# GSMGPSMC60.net
KiCad netlist of a schematic drawn in Altium Designer
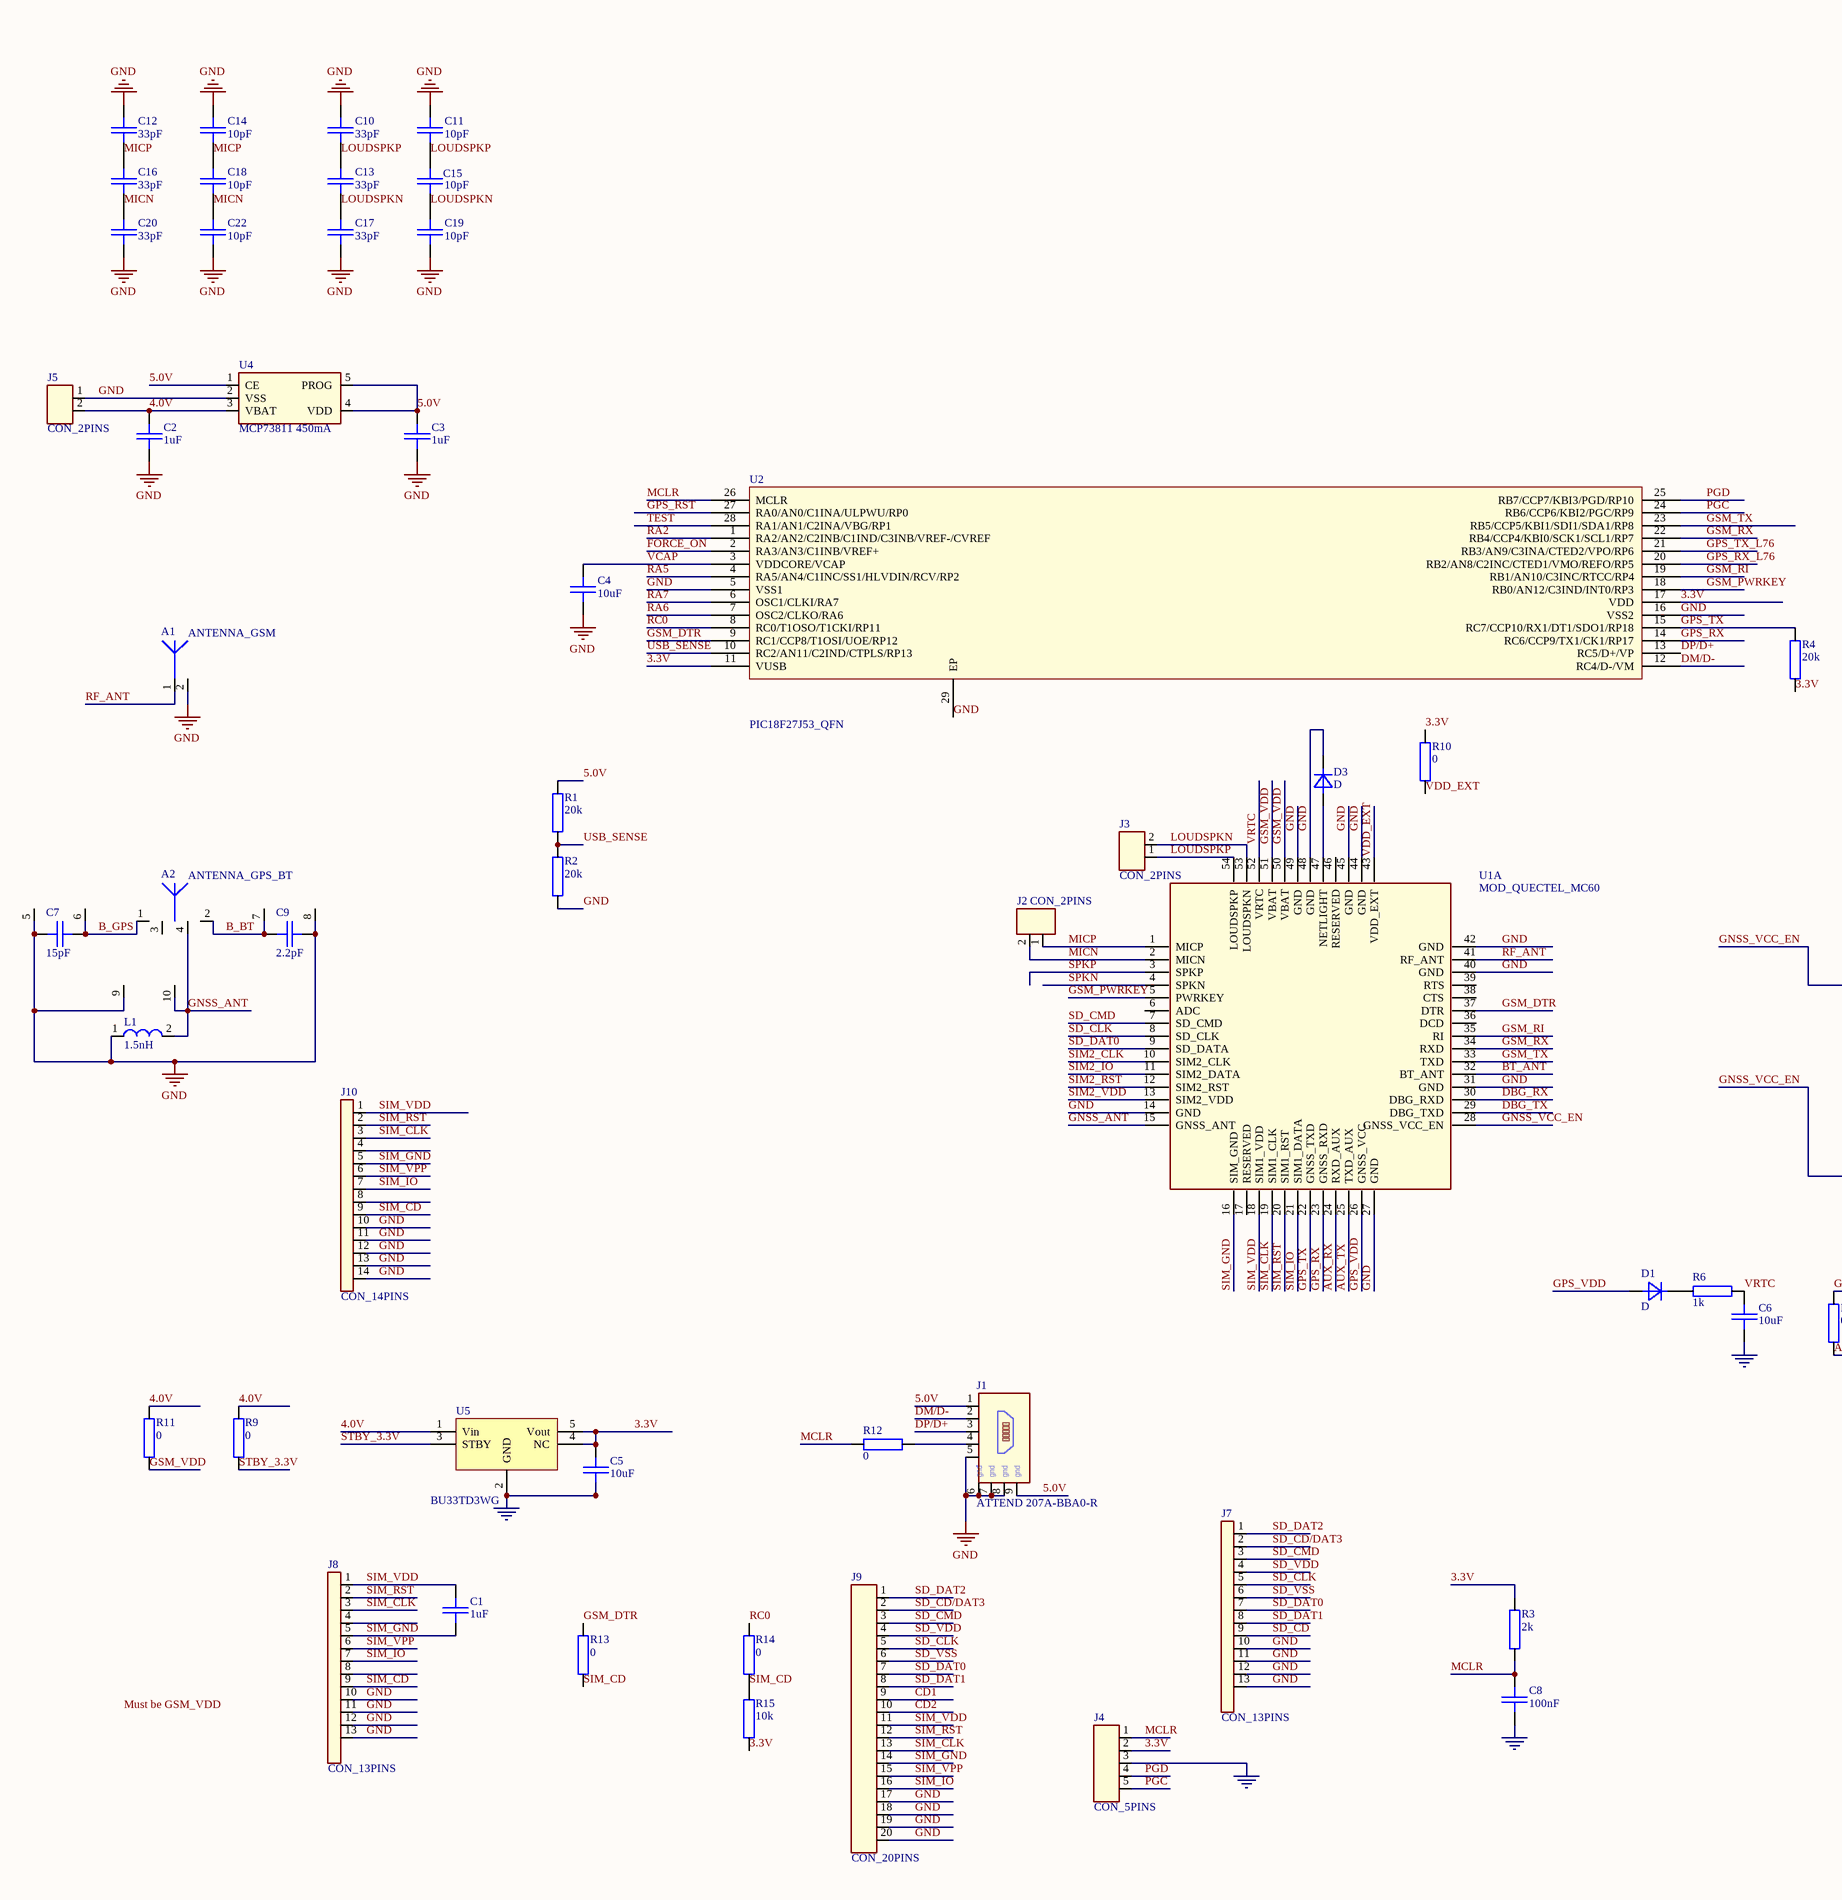
[diagram p0: GSMGPSMC60.SchDoc, left]
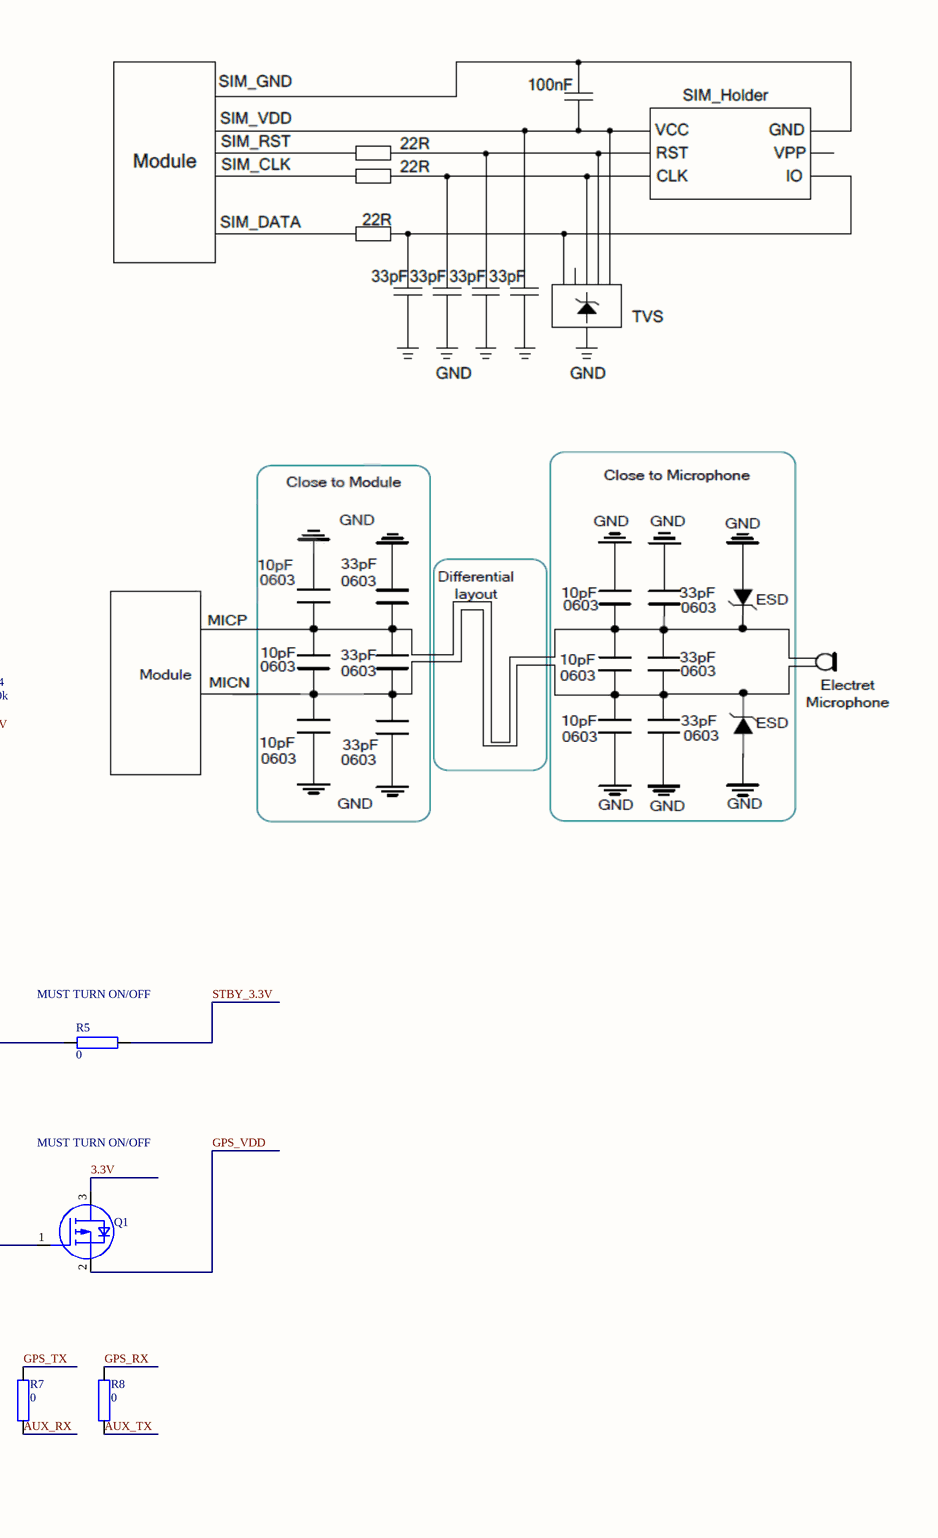
[diagram p1: GSMGPSMC60.SchDoc, right]

(export (version "E")
  (design (tool "Eeschema 10.0.6"))
  (components
    (comp (ref "A1")
      (value "ANTENNA_GSM")
      (footprint "SMD_CON_ANTENNA_GSM")
      (libsource (lib "DLV") (part "ANTENNA_2"))
    )
    (comp (ref "A2")
      (value "ANTENNA_GPS_BT")
      (footprint "SMD_CHIP_ANTENNA_GPS_BT - FLIP")
      (libsource (lib "DLV") (part "ANTENNA_GPS_BT"))
    )
    (comp (ref "C1") (value "1uF") (footprint "SMD_0603_CAPC1608X95N") (libsource (lib "DLV") (part "C")))
    (comp (ref "C2") (value "1uF") (footprint "SMD_0603_CAPC1608X95N") (libsource (lib "DLV") (part "C")))
    (comp (ref "C3") (value "1uF") (footprint "SMD_0603_CAPC1608X95N") (libsource (lib "DLV") (part "C")))
    (comp (ref "C4") (value "10uF") (footprint "SMD_0603_CAPC1608X95N") (libsource (lib "DLV") (part "C")))
    (comp (ref "C5") (value "10uF") (footprint "SMD_0603_CAPC1608X95N") (libsource (lib "DLV") (part "C")))
    (comp (ref "C6") (value "10uF") (footprint "SMD_0603_CAPC1608X95N") (libsource (lib "DLV") (part "C")))
    (comp (ref "C7")
      (value "15pF")
      (footprint "SMD_0402_CAPC1005X90N - ANTENNA")
      (libsource (lib "DLV") (part "C"))
    )
    (comp (ref "C8") (value "100nF") (footprint "SMD_0402_CAPC1005X90N") (libsource (lib "DLV") (part "C")))
    (comp (ref "C9")
      (value "2.2pF")
      (footprint "SMD_0201_CAPC0603X33N - ANTENNA")
      (libsource (lib "DLV") (part "C"))
    )
    (comp (ref "C10") (value "33pF") (footprint "SMD_0402_CAPC1005X90N") (libsource (lib "DLV") (part "C")))
    (comp (ref "C11") (value "10pF") (footprint "SMD_0402_CAPC1005X90N") (libsource (lib "DLV") (part "C")))
    (comp (ref "C12") (value "33pF") (footprint "SMD_0402_CAPC1005X90N") (libsource (lib "DLV") (part "C")))
    (comp (ref "C13") (value "33pF") (footprint "SMD_0402_CAPC1005X90N") (libsource (lib "DLV") (part "C")))
    (comp (ref "C14") (value "10pF") (footprint "SMD_0402_CAPC1005X90N") (libsource (lib "DLV") (part "C")))
    (comp (ref "C15") (value "10pF") (footprint "SMD_0402_CAPC1005X90N") (libsource (lib "DLV") (part "C")))
    (comp (ref "C16") (value "33pF") (footprint "SMD_0402_CAPC1005X90N") (libsource (lib "DLV") (part "C")))
    (comp (ref "C17") (value "33pF") (footprint "SMD_0402_CAPC1005X90N") (libsource (lib "DLV") (part "C")))
    (comp (ref "C18") (value "10pF") (footprint "SMD_0402_CAPC1005X90N") (libsource (lib "DLV") (part "C")))
    (comp (ref "C19") (value "10pF") (footprint "SMD_0402_CAPC1005X90N") (libsource (lib "DLV") (part "C")))
    (comp (ref "C20") (value "33pF") (footprint "SMD_0402_CAPC1005X90N") (libsource (lib "DLV") (part "C")))
    (comp (ref "C22") (value "10pF") (footprint "SMD_0402_CAPC1005X90N") (libsource (lib "DLV") (part "C")))
    (comp (ref "D1") (value "D") (footprint "SMD_SOD523_SOD1608X65N") (libsource (lib "DLV") (part "D")))
    (comp (ref "D3") (value "D") (footprint "SMD_LED_LAA67F") (libsource (lib "DLV") (part "D")))
    (comp (ref "J1")
      (value "ATTEND 207A-BBA0-R")
      (footprint "SMD_CON_MICRO_USB")
      (libsource (lib "DLV") (part "CON_USB_MINI"))
    )
    (comp (ref "J2")
      (value "CON_2PINS")
      (footprint "PTH_MIC_6MM_2.7MM_PITCH1.9")
      (libsource (lib "") (part "CON_2PINS_1"))
    )
    (comp (ref "J3")
      (value "CON_2PINS")
      (footprint "PTH_MIC_6MM_2.7MM_PITCH1.9")
      (libsource (lib "") (part "CON_2PINS_2"))
    )
    (comp (ref "J4") (value "CON_5PINS") (footprint "SIP5 - PGM") (libsource (lib "DLV") (part "CON_5PINS")))
    (comp (ref "J5")
      (value "CON_2PINS")
      (footprint "PTH_HDRV02W64P254_1X02")
      (libsource (lib "DLV") (part "CON_2PINS"))
    )
    (comp (ref "J7") (value "CON_13PINS") (footprint "NONE") (libsource (lib "DLV") (part "CON_13PINS")))
    (comp (ref "J8")
      (value "CON_13PINS")
      (footprint "SMD_CON-ATTEND_MICRO_SIM_115Q-BCA0")
      (libsource (lib "DLV") (part "CON_13PINS"))
    )
    (comp (ref "J9") (value "CON_20PINS") (footprint "NONE") (libsource (lib "DLV") (part "CON_20PINS")))
    (comp (ref "J10") (value "CON_14PINS") (footprint "NONE") (libsource (lib "DLV") (part "CON_14PINS")))
    (comp (ref "L1")
      (value "1.5nH")
      (footprint "SMD_0402_INDC1005X55N - ANTENNA")
      (libsource (lib "DLV") (part "L"))
    )
    (comp (ref "Q1")
      (value "BSH202")
      (footprint "SMD_SOT23_SOT95P240X120-3N")
      (fields
        (field (name "DB_PART_NUMBER") "TRA000000687")
        (field (name "DB_MANUFACTURER_PART") "NXP        BSH202")
      )
      (libsource (lib "EPIQ_DND_CIS") (part "MOS_P_D1_G1S2D3"))
    )
    (comp (ref "R1") (value "20k") (footprint "SMD_0402_RESC1005X37N") (libsource (lib "DLV") (part "R")))
    (comp (ref "R2") (value "20k") (footprint "SMD_0402_RESC1005X37N") (libsource (lib "DLV") (part "R")))
    (comp (ref "R3") (value "2k") (footprint "SMD_0402_RESC1005X37N") (libsource (lib "DLV") (part "R")))
    (comp (ref "R4") (value "20k") (footprint "SMD_0402_RESC1005X37N") (libsource (lib "DLV") (part "R")))
    (comp (ref "R5") (value "0") (footprint "SMD_0402_RESC1005X37N") (libsource (lib "DLV") (part "R")))
    (comp (ref "R6") (value "1k") (footprint "SMD_0603_RESC1608X55N") (libsource (lib "DLV") (part "R")))
    (comp (ref "R7") (value "0") (footprint "SMD_0603_RESC1608X55N") (libsource (lib "DLV") (part "R")))
    (comp (ref "R8") (value "0") (footprint "SMD_0603_RESC1608X55N") (libsource (lib "DLV") (part "R")))
    (comp (ref "R9") (value "0") (footprint "SMD_0402_RESC1005X37N") (libsource (lib "DLV") (part "R")))
    (comp (ref "R10") (value "0") (footprint "SMD_0402_RESC1005X37N") (libsource (lib "DLV") (part "R")))
    (comp (ref "R11") (value "0") (footprint "SMD_0402_RESC1005X37N") (libsource (lib "DLV") (part "R")))
    (comp (ref "R12") (value "0") (footprint "SMD_0402_RESC1005X37N") (libsource (lib "DLV") (part "R")))
    (comp (ref "R13") (value "0") (footprint "SMD_0402_RESC1005X37N") (libsource (lib "DLV") (part "R")))
    (comp (ref "R14") (value "0") (footprint "SMD_0402_RESC1005X37N") (libsource (lib "DLV") (part "R")))
    (comp (ref "R15") (value "10k") (footprint "SMD_0402_RESC1005X37N") (libsource (lib "DLV") (part "R")))
    (comp (ref "U1")
      (value "MOD_QUECTEL_MC60")
      (footprint "SMD_MOD_MC60")
      (libsource (lib "DLV") (part "MOD_QUECTEL_MC60"))
    )
    (comp (ref "U2")
      (value "PIC18F27J53_QFN")
      (footprint "SMD_QFN65P600X600X100-29AN")
      (libsource (lib "DLV") (part "IC_PIC18F27J53_QFN"))
    )
    (comp (ref "U4")
      (value "MCP73811 450mA")
      (footprint "SMD_SOT26_SOT95P285X140-5N - DLV")
      (description "MCP73812")
      (fields
        (field (name "DB_PART_NUMBER") "PSU000000127")
        (field (name "DB_MANUFACTURER_PART") "ROHM        BD33KA5WF-E2")
        (field (name "DB_APPROVED_BY") "VSN")
      )
      (libsource (lib "DLV") (part "IC_MCP73812"))
    )
    (comp (ref "U5")
      (value "BU33TD3WG")
      (footprint "SMD_SOT26_SOT95P285X140-5N - DLV")
      (libsource (lib "DLV") (part "IC_BU33TD3WG"))
    )
  )
  (nets
    (net (code "1") (name "/3.3V") (class "Default")
      (node (ref "C5") (pin "1") (pinfunction "1_1") (pintype "passive"))
      (node (ref "J4") (pin "2") (pinfunction "2_2") (pintype "passive"))
      (node (ref "Q1") (pin "3") (pinfunction "D_3") (pintype "passive"))
      (node (ref "R10") (pin "2") (pinfunction "2_2") (pintype "passive"))
      (node (ref "R15") (pin "2") (pinfunction "2_2") (pintype "passive"))
      (node (ref "R3") (pin "1") (pinfunction "1_1") (pintype "passive"))
      (node (ref "R4") (pin "1") (pinfunction "1_1") (pintype "passive"))
      (node (ref "U2") (pin "11") (pinfunction "VUSB_11") (pintype "passive"))
      (node (ref "U2") (pin "17") (pinfunction "VDD_17") (pintype "passive"))
      (node (ref "U5") (pin "4") (pinfunction "NC_4") (pintype "passive"))
      (node (ref "U5") (pin "5") (pinfunction "Vout_5") (pintype "passive"))
    )
    (net (code "2") (name "/4.0V") (class "Default")
      (node (ref "C2") (pin "1") (pinfunction "1_1") (pintype "passive"))
      (node (ref "J5") (pin "2") (pinfunction "2_2") (pintype "passive"))
      (node (ref "R11") (pin "1") (pinfunction "1_1") (pintype "passive"))
      (node (ref "R9") (pin "1") (pinfunction "1_1") (pintype "passive"))
      (node (ref "U4") (pin "3") (pinfunction "VBAT_3") (pintype "passive"))
      (node (ref "U5") (pin "1") (pinfunction "Vin_1") (pintype "passive"))
    )
    (net (code "3") (name "/5.0V") (class "Default")
      (node (ref "C3") (pin "1") (pinfunction "1_1") (pintype "passive"))
      (node (ref "J1") (pin "1") (pinfunction "1_1") (pintype "passive"))
      (node (ref "J1") (pin "9") (pinfunction "9_9") (pintype "passive"))
      (node (ref "R1") (pin "2") (pinfunction "2_2") (pintype "passive"))
      (node (ref "U4") (pin "1") (pinfunction "CE_1") (pintype "passive"))
      (node (ref "U4") (pin "4") (pinfunction "VDD_4") (pintype "passive"))
      (node (ref "U4") (pin "5") (pinfunction "PROG_5") (pintype "passive"))
    )
    (net (code "4") (name "/AUX_RX") (class "Default")
      (node (ref "R7") (pin "2") (pinfunction "2_2") (pintype "passive"))
      (node (ref "U1") (pin "24") (pinfunction "RXD_AUX_24") (pintype "passive"))
    )
    (net (code "5") (name "/AUX_TX") (class "Default")
      (node (ref "R8") (pin "1") (pinfunction "1_1") (pintype "passive"))
      (node (ref "U1") (pin "25") (pinfunction "TXD_AUX_25") (pintype "passive"))
    )
    (net (code "6") (name "/BT_ANT") (class "Default")
      (node (ref "U1") (pin "32") (pinfunction "BT_ANT_32") (pintype "passive"))
    )
    (net (code "7") (name "/B_BT") (class "Default")
      (node (ref "A2") (pin "2") (pinfunction "2_2") (pintype "passive"))
      (node (ref "A2") (pin "7") (pinfunction "7_7") (pintype "passive"))
      (node (ref "C9") (pin "1") (pinfunction "1_1") (pintype "passive"))
    )
    (net (code "8") (name "/B_GPS") (class "Default")
      (node (ref "A2") (pin "1") (pinfunction "1_1") (pintype "passive"))
      (node (ref "A2") (pin "6") (pinfunction "6_6") (pintype "passive"))
      (node (ref "C7") (pin "2") (pinfunction "2_2") (pintype "passive"))
    )
    (net (code "9") (name "/CD1") (class "Default")
      (node (ref "J9") (pin "9") (pinfunction "9_9") (pintype "passive"))
    )
    (net (code "10") (name "/CD2") (class "Default")
      (node (ref "J9") (pin "10") (pinfunction "10_10") (pintype "passive"))
    )
    (net (code "11") (name "/DBG_RX") (class "Default")
      (node (ref "U1") (pin "30") (pinfunction "DBG_RXD_30") (pintype "passive"))
    )
    (net (code "12") (name "/DBG_TX") (class "Default")
      (node (ref "U1") (pin "29") (pinfunction "DBG_TXD_29") (pintype "passive"))
    )
    (net (code "13") (name "/DM{slash}D-") (class "Default")
      (node (ref "J1") (pin "2") (pinfunction "2_2") (pintype "passive"))
      (node (ref "U2") (pin "12") (pinfunction "RC4/D-/VM_12") (pintype "passive"))
    )
    (net (code "14") (name "/DP{slash}D+") (class "Default")
      (node (ref "J1") (pin "3") (pinfunction "3_3") (pintype "passive"))
      (node (ref "U2") (pin "13") (pinfunction "RC5/D+/VP_13") (pintype "passive"))
    )
    (net (code "15") (name "/FORCE_ON") (class "Default")
      (node (ref "U2") (pin "2") (pinfunction "RA3/AN3/C1INB/VREF+_2") (pintype "passive"))
    )
    (net (code "16") (name "/GNSS_ANT") (class "Default")
      (node (ref "A2") (pin "10") (pinfunction "10_10") (pintype "passive"))
      (node (ref "A2") (pin "4") (pinfunction "4_4") (pintype "passive"))
      (node (ref "L1") (pin "2") (pinfunction "2_2") (pintype "passive"))
      (node (ref "U1") (pin "15") (pinfunction "GNSS_ANT_15") (pintype "passive"))
    )
    (net (code "17") (name "/GNSS_VCC_EN") (class "Default")
      (node (ref "Q1") (pin "1") (pinfunction "G_1") (pintype "passive"))
      (node (ref "R5") (pin "1") (pinfunction "1_1") (pintype "passive"))
      (node (ref "U1") (pin "28") (pinfunction "GNSS_VCC_EN_28") (pintype "passive"))
    )
    (net (code "18") (name "/GPS_RST") (class "Default")
      (node (ref "U2") (pin "27") (pinfunction "RA0/AN0/C1INA/ULPWU/RP0_27") (pintype "passive"))
    )
    (net (code "19") (name "/GPS_RX") (class "Default")
      (node (ref "R8") (pin "2") (pinfunction "2_2") (pintype "passive"))
      (node (ref "U1") (pin "23") (pinfunction "GNSS_RXD_23") (pintype "passive"))
      (node (ref "U2") (pin "14") (pinfunction "RC6/CCP9/TX1/CK1/RP17_14") (pintype "passive"))
    )
    (net (code "20") (name "/GPS_RX_L76") (class "Default")
      (node (ref "U2") (pin "20") (pinfunction "RB2/AN8/C2INC/CTED1/VMO/REFO/RP5_20") (pintype "passive"))
    )
    (net (code "21") (name "/GPS_TX") (class "Default")
      (node (ref "R4") (pin "2") (pinfunction "2_2") (pintype "passive"))
      (node (ref "R7") (pin "1") (pinfunction "1_1") (pintype "passive"))
      (node (ref "U1") (pin "22") (pinfunction "GNSS_TXD_22") (pintype "passive"))
      (node (ref "U2") (pin "15") (pinfunction "RC7/CCP10/RX1/DT1/SDO1/RP18_15") (pintype "passive"))
    )
    (net (code "22") (name "/GPS_TX_L76") (class "Default")
      (node (ref "U2") (pin "21") (pinfunction "RB3/AN9/C3INA/CTED2/VPO/RP6_21") (pintype "passive"))
    )
    (net (code "23") (name "/GPS_VDD") (class "Default")
      (node (ref "D1") (pin "2") (pinfunction "A_2") (pintype "passive"))
      (node (ref "Q1") (pin "2") (pinfunction "S_2") (pintype "passive"))
      (node (ref "U1") (pin "26") (pinfunction "GNSS_VCC_26") (pintype "passive"))
    )
    (net (code "24") (name "/GSM_DTR") (class "Default")
      (node (ref "R13") (pin "1") (pinfunction "1_1") (pintype "passive"))
      (node (ref "U1") (pin "37") (pinfunction "DTR_37") (pintype "passive"))
      (node (ref "U2") (pin "9") (pinfunction "RC1/CCP8/T1OSI/UOE/RP12_9") (pintype "passive"))
    )
    (net (code "25") (name "/GSM_PWRKEY") (class "Default")
      (node (ref "U1") (pin "5") (pinfunction "PWRKEY_5") (pintype "passive"))
      (node (ref "U2") (pin "18") (pinfunction "RB0/AN12/C3IND/INT0/RP3_18") (pintype "passive"))
    )
    (net (code "26") (name "/GSM_RI") (class "Default")
      (node (ref "U1") (pin "35") (pinfunction "RI_35") (pintype "passive"))
      (node (ref "U2") (pin "19") (pinfunction "RB1/AN10/C3INC/RTCC/RP4_19") (pintype "passive"))
    )
    (net (code "27") (name "/GSM_RX") (class "Default")
      (node (ref "U1") (pin "34") (pinfunction "RXD_34") (pintype "passive"))
      (node (ref "U2") (pin "22") (pinfunction "RB4/CCP4/KBI0/SCK1/SCL1/RP7_22") (pintype "passive"))
    )
    (net (code "28") (name "/GSM_TX") (class "Default")
      (node (ref "U1") (pin "33") (pinfunction "TXD_33") (pintype "passive"))
      (node (ref "U2") (pin "23") (pinfunction "RB5/CCP5/KBI1/SDI1/SDA1/RP8_23") (pintype "passive"))
    )
    (net (code "29") (name "/GSM_VDD") (class "Default")
      (node (ref "R11") (pin "2") (pinfunction "2_2") (pintype "passive"))
      (node (ref "U1") (pin "50") (pinfunction "VBAT_50") (pintype "passive"))
      (node (ref "U1") (pin "51") (pinfunction "VBAT_51") (pintype "passive"))
    )
    (net (code "30") (name "/LOUDSPKN") (class "Default")
      (node (ref "C13") (pin "2") (pinfunction "2_2") (pintype "passive"))
      (node (ref "C15") (pin "2") (pinfunction "2_2") (pintype "passive"))
      (node (ref "C17") (pin "1") (pinfunction "1_1") (pintype "passive"))
      (node (ref "C19") (pin "1") (pinfunction "1_1") (pintype "passive"))
      (node (ref "J3") (pin "2") (pinfunction "2_2") (pintype "passive"))
      (node (ref "U1") (pin "53") (pinfunction "LOUDSPKN_53") (pintype "passive"))
    )
    (net (code "31") (name "/LOUDSPKP") (class "Default")
      (node (ref "C10") (pin "2") (pinfunction "2_2") (pintype "passive"))
      (node (ref "C11") (pin "2") (pinfunction "2_2") (pintype "passive"))
      (node (ref "C13") (pin "1") (pinfunction "1_1") (pintype "passive"))
      (node (ref "C15") (pin "1") (pinfunction "1_1") (pintype "passive"))
      (node (ref "J3") (pin "1") (pinfunction "1_1") (pintype "passive"))
      (node (ref "U1") (pin "54") (pinfunction "LOUDSPKP_54") (pintype "passive"))
    )
    (net (code "32") (name "/MCLR") (class "Default")
      (node (ref "C8") (pin "1") (pinfunction "1_1") (pintype "passive"))
      (node (ref "J4") (pin "1") (pinfunction "1_1") (pintype "passive"))
      (node (ref "R12") (pin "2") (pinfunction "2_2") (pintype "passive"))
      (node (ref "R3") (pin "2") (pinfunction "2_2") (pintype "passive"))
      (node (ref "U2") (pin "26") (pinfunction "MCLR_26") (pintype "passive"))
    )
    (net (code "33") (name "/MICN") (class "Default")
      (node (ref "C16") (pin "2") (pinfunction "2_2") (pintype "passive"))
      (node (ref "C18") (pin "2") (pinfunction "2_2") (pintype "passive"))
      (node (ref "C20") (pin "1") (pinfunction "1_1") (pintype "passive"))
      (node (ref "C22") (pin "1") (pinfunction "1_1") (pintype "passive"))
      (node (ref "J2") (pin "2") (pinfunction "2_2") (pintype "passive"))
      (node (ref "U1") (pin "2") (pinfunction "MICN_2") (pintype "passive"))
    )
    (net (code "34") (name "/MICP") (class "Default")
      (node (ref "C12") (pin "2") (pinfunction "2_2") (pintype "passive"))
      (node (ref "C14") (pin "2") (pinfunction "2_2") (pintype "passive"))
      (node (ref "C16") (pin "1") (pinfunction "1_1") (pintype "passive"))
      (node (ref "C18") (pin "1") (pinfunction "1_1") (pintype "passive"))
      (node (ref "J2") (pin "1") (pinfunction "1_1") (pintype "passive"))
      (node (ref "U1") (pin "1") (pinfunction "MICP_1") (pintype "passive"))
    )
    (net (code "36") (name "/PGC") (class "Default")
      (node (ref "J4") (pin "5") (pinfunction "5_5") (pintype "passive"))
      (node (ref "U2") (pin "24") (pinfunction "RB6/CCP6/KBI2/PGC/RP9_24") (pintype "passive"))
    )
    (net (code "37") (name "/PGD") (class "Default")
      (node (ref "J4") (pin "4") (pinfunction "4_4") (pintype "passive"))
      (node (ref "U2") (pin "25") (pinfunction "RB7/CCP7/KBI3/PGD/RP10_25") (pintype "passive"))
    )
    (net (code "38") (name "/RA2") (class "Default")
      (node (ref "U2") (pin "1") (pinfunction "RA2/AN2/C2INB/C1IND/C3INB/VREF-/CVREF_1") (pintype "passive"))
    )
    (net (code "39") (name "/RA5") (class "Default")
      (node (ref "U2") (pin "4") (pinfunction "RA5/AN4/C1INC/SS1/HLVDIN/RCV/RP2_4") (pintype "passive"))
    )
    (net (code "40") (name "/RA6") (class "Default")
      (node (ref "U2") (pin "7") (pinfunction "OSC2/CLKO/RA6_7") (pintype "passive"))
    )
    (net (code "41") (name "/RA7") (class "Default")
      (node (ref "U2") (pin "6") (pinfunction "OSC1/CLKI/RA7_6") (pintype "passive"))
    )
    (net (code "42") (name "/RC0") (class "Default")
      (node (ref "R14") (pin "1") (pinfunction "1_1") (pintype "passive"))
      (node (ref "U2") (pin "8") (pinfunction "RC0/T1OSO/T1CKI/RP11_8") (pintype "passive"))
    )
    (net (code "43") (name "/RF_ANT") (class "Default")
      (node (ref "A1") (pin "1") (pinfunction "1_1") (pintype "passive"))
      (node (ref "U1") (pin "41") (pinfunction "RF_ANT_41") (pintype "passive"))
    )
    (net (code "44") (name "/SD_CD") (class "Default")
      (node (ref "J7") (pin "9") (pinfunction "9_9") (pintype "passive"))
    )
    (net (code "45") (name "/SD_CD{slash}DAT3") (class "Default")
      (node (ref "J7") (pin "2") (pinfunction "2_2") (pintype "passive"))
      (node (ref "J9") (pin "2") (pinfunction "2_2") (pintype "passive"))
    )
    (net (code "46") (name "/SD_CLK") (class "Default")
      (node (ref "J7") (pin "5") (pinfunction "5_5") (pintype "passive"))
      (node (ref "J9") (pin "5") (pinfunction "5_5") (pintype "passive"))
      (node (ref "U1") (pin "8") (pinfunction "SD_CLK_8") (pintype "passive"))
    )
    (net (code "47") (name "/SD_CMD") (class "Default")
      (node (ref "J7") (pin "3") (pinfunction "3_3") (pintype "passive"))
      (node (ref "J9") (pin "3") (pinfunction "3_3") (pintype "passive"))
      (node (ref "U1") (pin "7") (pinfunction "SD_CMD_7") (pintype "passive"))
    )
    (net (code "48") (name "/SD_DAT0") (class "Default")
      (node (ref "J7") (pin "7") (pinfunction "7_7") (pintype "passive"))
      (node (ref "J9") (pin "7") (pinfunction "7_7") (pintype "passive"))
      (node (ref "U1") (pin "9") (pinfunction "SD_DATA_9") (pintype "passive"))
    )
    (net (code "49") (name "/SD_DAT1") (class "Default")
      (node (ref "J7") (pin "8") (pinfunction "8_8") (pintype "passive"))
      (node (ref "J9") (pin "8") (pinfunction "8_8") (pintype "passive"))
    )
    (net (code "50") (name "/SD_DAT2") (class "Default")
      (node (ref "J7") (pin "1") (pinfunction "1_1") (pintype "passive"))
      (node (ref "J9") (pin "1") (pinfunction "1_1") (pintype "passive"))
    )
    (net (code "51") (name "/SD_VDD") (class "Default")
      (node (ref "J7") (pin "4") (pinfunction "4_4") (pintype "passive"))
      (node (ref "J9") (pin "4") (pinfunction "4_4") (pintype "passive"))
    )
    (net (code "52") (name "/SD_VSS") (class "Default")
      (node (ref "J7") (pin "6") (pinfunction "6_6") (pintype "passive"))
      (node (ref "J9") (pin "6") (pinfunction "6_6") (pintype "passive"))
    )
    (net (code "53") (name "/SIM2_CLK") (class "Default")
      (node (ref "U1") (pin "10") (pinfunction "SIM2_CLK_10") (pintype "passive"))
    )
    (net (code "54") (name "/SIM2_IO") (class "Default")
      (node (ref "U1") (pin "11") (pinfunction "SIM2_DATA_11") (pintype "passive"))
    )
    (net (code "55") (name "/SIM2_RST") (class "Default")
      (node (ref "U1") (pin "12") (pinfunction "SIM2_RST_12") (pintype "passive"))
    )
    (net (code "56") (name "/SIM2_VDD") (class "Default")
      (node (ref "U1") (pin "13") (pinfunction "SIM2_VDD_13") (pintype "passive"))
    )
    (net (code "57") (name "/SIM_CD") (class "Default")
      (node (ref "J10") (pin "9") (pinfunction "9_9") (pintype "passive"))
      (node (ref "J8") (pin "9") (pinfunction "9_9") (pintype "passive"))
      (node (ref "R13") (pin "2") (pinfunction "2_2") (pintype "passive"))
      (node (ref "R14") (pin "2") (pinfunction "2_2") (pintype "passive"))
      (node (ref "R15") (pin "1") (pinfunction "1_1") (pintype "passive"))
    )
    (net (code "58") (name "/SIM_CLK") (class "Default")
      (node (ref "J10") (pin "3") (pinfunction "3_3") (pintype "passive"))
      (node (ref "J8") (pin "3") (pinfunction "3_3") (pintype "passive"))
      (node (ref "J9") (pin "13") (pinfunction "13_13") (pintype "passive"))
      (node (ref "U1") (pin "19") (pinfunction "SIM1_CLK_19") (pintype "passive"))
    )
    (net (code "59") (name "/SIM_GND") (class "Default")
      (node (ref "C1") (pin "2") (pinfunction "2_2") (pintype "passive"))
      (node (ref "J10") (pin "5") (pinfunction "5_5") (pintype "passive"))
      (node (ref "J8") (pin "5") (pinfunction "5_5") (pintype "passive"))
      (node (ref "J9") (pin "14") (pinfunction "14_14") (pintype "passive"))
      (node (ref "U1") (pin "16") (pinfunction "SIM_GND_16") (pintype "passive"))
    )
    (net (code "60") (name "/SIM_IO") (class "Default")
      (node (ref "J10") (pin "7") (pinfunction "7_7") (pintype "passive"))
      (node (ref "J8") (pin "7") (pinfunction "7_7") (pintype "passive"))
      (node (ref "J9") (pin "16") (pinfunction "16_16") (pintype "passive"))
      (node (ref "U1") (pin "21") (pinfunction "SIM1_DATA_21") (pintype "passive"))
    )
    (net (code "61") (name "/SIM_RST") (class "Default")
      (node (ref "J10") (pin "2") (pinfunction "2_2") (pintype "passive"))
      (node (ref "J8") (pin "2") (pinfunction "2_2") (pintype "passive"))
      (node (ref "J9") (pin "12") (pinfunction "12_12") (pintype "passive"))
      (node (ref "U1") (pin "20") (pinfunction "SIM1_RST_20") (pintype "passive"))
    )
    (net (code "62") (name "/SIM_VDD") (class "Default")
      (node (ref "C1") (pin "1") (pinfunction "1_1") (pintype "passive"))
      (node (ref "J10") (pin "1") (pinfunction "1_1") (pintype "passive"))
      (node (ref "J8") (pin "1") (pinfunction "1_1") (pintype "passive"))
      (node (ref "J9") (pin "11") (pinfunction "11_11") (pintype "passive"))
      (node (ref "U1") (pin "18") (pinfunction "SIM1_VDD_18") (pintype "passive"))
    )
    (net (code "63") (name "/SIM_VPP") (class "Default")
      (node (ref "J10") (pin "6") (pinfunction "6_6") (pintype "passive"))
      (node (ref "J8") (pin "6") (pinfunction "6_6") (pintype "passive"))
      (node (ref "J9") (pin "15") (pinfunction "15_15") (pintype "passive"))
    )
    (net (code "64") (name "/SPKN") (class "Default")
      (node (ref "U1") (pin "4") (pinfunction "SPKN_4") (pintype "passive"))
    )
    (net (code "65") (name "/SPKP") (class "Default")
      (node (ref "U1") (pin "3") (pinfunction "SPKP_3") (pintype "passive"))
    )
    (net (code "66") (name "/STBY_3.3V") (class "Default")
      (node (ref "R5") (pin "2") (pinfunction "2_2") (pintype "passive"))
      (node (ref "R9") (pin "2") (pinfunction "2_2") (pintype "passive"))
      (node (ref "U5") (pin "3") (pinfunction "STBY_3") (pintype "passive"))
    )
    (net (code "67") (name "/TEST") (class "Default")
      (node (ref "U2") (pin "28") (pinfunction "RA1/AN1/C2INA/VBG/RP1_28") (pintype "passive"))
    )
    (net (code "68") (name "/USB_SENSE") (class "Default")
      (node (ref "R1") (pin "1") (pinfunction "1_1") (pintype "passive"))
      (node (ref "R2") (pin "2") (pinfunction "2_2") (pintype "passive"))
      (node (ref "U2") (pin "10") (pinfunction "RC2/AN11/C2IND/CTPLS/RP13_10") (pintype "passive"))
    )
    (net (code "69") (name "/VCAP") (class "Default")
      (node (ref "C4") (pin "1") (pinfunction "1_1") (pintype "passive"))
      (node (ref "U2") (pin "3") (pinfunction "VDDCORE/VCAP_3") (pintype "passive"))
    )
    (net (code "70") (name "/VDD_EXT") (class "Default")
      (node (ref "R10") (pin "1") (pinfunction "1_1") (pintype "passive"))
      (node (ref "U1") (pin "43") (pinfunction "VDD_EXT_43") (pintype "passive"))
    )
    (net (code "71") (name "/VRTC") (class "Default")
      (node (ref "C6") (pin "1") (pinfunction "1_1") (pintype "passive"))
      (node (ref "R6") (pin "1") (pinfunction "1_1") (pintype "passive"))
      (node (ref "U1") (pin "52") (pinfunction "VRTC_52") (pintype "passive"))
    )
    (net (code "72") (name "GND") (class "Default")
      (node (ref "A1") (pin "2") (pinfunction "2_2") (pintype "passive"))
      (node (ref "A2") (pin "5") (pinfunction "5_5") (pintype "passive"))
      (node (ref "A2") (pin "8") (pinfunction "8_8") (pintype "passive"))
      (node (ref "A2") (pin "9") (pinfunction "9_9") (pintype "passive"))
      (node (ref "C10") (pin "1") (pinfunction "1_1") (pintype "passive"))
      (node (ref "C11") (pin "1") (pinfunction "1_1") (pintype "passive"))
      (node (ref "C12") (pin "1") (pinfunction "1_1") (pintype "passive"))
      (node (ref "C14") (pin "1") (pinfunction "1_1") (pintype "passive"))
      (node (ref "C17") (pin "2") (pinfunction "2_2") (pintype "passive"))
      (node (ref "C19") (pin "2") (pinfunction "2_2") (pintype "passive"))
      (node (ref "C2") (pin "2") (pinfunction "2_2") (pintype "passive"))
      (node (ref "C20") (pin "2") (pinfunction "2_2") (pintype "passive"))
      (node (ref "C22") (pin "2") (pinfunction "2_2") (pintype "passive"))
      (node (ref "C3") (pin "2") (pinfunction "2_2") (pintype "passive"))
      (node (ref "C4") (pin "2") (pinfunction "2_2") (pintype "passive"))
      (node (ref "C5") (pin "2") (pinfunction "2_2") (pintype "passive"))
      (node (ref "C6") (pin "2") (pinfunction "2_2") (pintype "passive"))
      (node (ref "C7") (pin "1") (pinfunction "1_1") (pintype "passive"))
      (node (ref "C8") (pin "2") (pinfunction "2_2") (pintype "passive"))
      (node (ref "C9") (pin "2") (pinfunction "2_2") (pintype "passive"))
      (node (ref "D3") (pin "1") (pinfunction "C_1") (pintype "passive"))
      (node (ref "J1") (pin "5") (pinfunction "5_5") (pintype "passive"))
      (node (ref "J1") (pin "6") (pinfunction "6_6") (pintype "passive"))
      (node (ref "J1") (pin "7") (pinfunction "7_7") (pintype "passive"))
      (node (ref "J1") (pin "8") (pinfunction "8_8") (pintype "passive"))
      (node (ref "J10") (pin "10") (pinfunction "10_10") (pintype "passive"))
      (node (ref "J10") (pin "11") (pinfunction "11_11") (pintype "passive"))
      (node (ref "J10") (pin "12") (pinfunction "12_12") (pintype "passive"))
      (node (ref "J10") (pin "13") (pinfunction "13_13") (pintype "passive"))
      (node (ref "J10") (pin "14") (pinfunction "14_14") (pintype "passive"))
      (node (ref "J4") (pin "3") (pinfunction "3_3") (pintype "passive"))
      (node (ref "J5") (pin "1") (pinfunction "1_1") (pintype "passive"))
      (node (ref "J7") (pin "10") (pinfunction "10_10") (pintype "passive"))
      (node (ref "J7") (pin "11") (pinfunction "11_11") (pintype "passive"))
      (node (ref "J7") (pin "12") (pinfunction "12_12") (pintype "passive"))
      (node (ref "J7") (pin "13") (pinfunction "13_13") (pintype "passive"))
      (node (ref "J8") (pin "10") (pinfunction "10_10") (pintype "passive"))
      (node (ref "J8") (pin "11") (pinfunction "11_11") (pintype "passive"))
      (node (ref "J8") (pin "12") (pinfunction "12_12") (pintype "passive"))
      (node (ref "J8") (pin "13") (pinfunction "13_13") (pintype "passive"))
      (node (ref "J9") (pin "17") (pinfunction "17_17") (pintype "passive"))
      (node (ref "J9") (pin "18") (pinfunction "18_18") (pintype "passive"))
      (node (ref "J9") (pin "19") (pinfunction "19_19") (pintype "passive"))
      (node (ref "J9") (pin "20") (pinfunction "20_20") (pintype "passive"))
      (node (ref "L1") (pin "1") (pinfunction "1_1") (pintype "passive"))
      (node (ref "R2") (pin "1") (pinfunction "1_1") (pintype "passive"))
      (node (ref "U1") (pin "14") (pinfunction "GND_14") (pintype "passive"))
      (node (ref "U1") (pin "27") (pinfunction "GND_27") (pintype "passive"))
      (node (ref "U1") (pin "31") (pinfunction "GND_31") (pintype "passive"))
      (node (ref "U1") (pin "40") (pinfunction "GND_40") (pintype "passive"))
      (node (ref "U1") (pin "42") (pinfunction "GND_42") (pintype "passive"))
      (node (ref "U1") (pin "44") (pinfunction "GND_44") (pintype "passive"))
      (node (ref "U1") (pin "45") (pinfunction "GND_45") (pintype "passive"))
      (node (ref "U1") (pin "48") (pinfunction "GND_48") (pintype "passive"))
      (node (ref "U1") (pin "49") (pinfunction "GND_49") (pintype "passive"))
      (node (ref "U2") (pin "16") (pinfunction "VSS2_16") (pintype "passive"))
      (node (ref "U2") (pin "29") (pinfunction "EP_29") (pintype "passive"))
      (node (ref "U2") (pin "5") (pinfunction "VSS1_5") (pintype "passive"))
      (node (ref "U4") (pin "2") (pinfunction "VSS_2") (pintype "passive"))
      (node (ref "U5") (pin "2") (pinfunction "GND_2") (pintype "passive"))
    )
    (net (code "73") (name "Net-(D1-C)") (class "Default")
      (node (ref "D1") (pin "1") (pinfunction "C_1") (pintype "passive"))
      (node (ref "R6") (pin "2") (pinfunction "2_2") (pintype "passive"))
    )
    (net (code "74") (name "Net-(D3-A)") (class "Default")
      (node (ref "D3") (pin "2") (pinfunction "A_2") (pintype "passive"))
      (node (ref "U1") (pin "47") (pinfunction "NETLIGHT_47") (pintype "passive"))
    )
    (net (code "75") (name "Net-(J1-Pad4)") (class "Default")
      (node (ref "J1") (pin "4") (pinfunction "4_4") (pintype "passive"))
      (node (ref "R12") (pin "1") (pinfunction "1_1") (pintype "passive"))
    )
    (net (code "76") (name "unconnected-(A2-Pad3)") (class "Default")
      (node (ref "A2") (pin "3") (pinfunction "3_3") (pintype "passive"))
    )
    (net (code "77") (name "unconnected-(J8-Pad4)") (class "Default")
      (node (ref "J8") (pin "4") (pinfunction "4_4") (pintype "passive"))
    )
    (net (code "78") (name "unconnected-(J8-Pad8)") (class "Default")
      (node (ref "J8") (pin "8") (pinfunction "8_8") (pintype "passive"))
    )
    (net (code "79") (name "unconnected-(J10-Pad4)") (class "Default")
      (node (ref "J10") (pin "4") (pinfunction "4_4") (pintype "passive"))
    )
    (net (code "80") (name "unconnected-(J10-Pad8)") (class "Default")
      (node (ref "J10") (pin "8") (pinfunction "8_8") (pintype "passive"))
    )
    (net (code "81") (name "unconnected-(U1A-ADC-Pad6)") (class "Default")
      (node (ref "U1") (pin "6") (pinfunction "ADC_6") (pintype "passive"))
    )
    (net (code "82") (name "unconnected-(U1A-CTS-Pad38)") (class "Default")
      (node (ref "U1") (pin "38") (pinfunction "CTS_38") (pintype "passive"))
    )
    (net (code "83") (name "unconnected-(U1A-DCD-Pad36)") (class "Default")
      (node (ref "U1") (pin "36") (pinfunction "DCD_36") (pintype "passive"))
    )
    (net (code "84") (name "unconnected-(U1A-RESERVED-Pad17)") (class "Default")
      (node (ref "U1") (pin "17") (pinfunction "RESERVED_17") (pintype "passive"))
    )
    (net (code "85") (name "unconnected-(U1A-RESERVED-Pad46)") (class "Default")
      (node (ref "U1") (pin "46") (pinfunction "RESERVED_46") (pintype "passive"))
    )
    (net (code "86") (name "unconnected-(U1A-RTS-Pad39)") (class "Default")
      (node (ref "U1") (pin "39") (pinfunction "RTS_39") (pintype "passive"))
    )
  )
)
